# Sheet1.net
KiCad netlist of a schematic drawn in Altium Designer
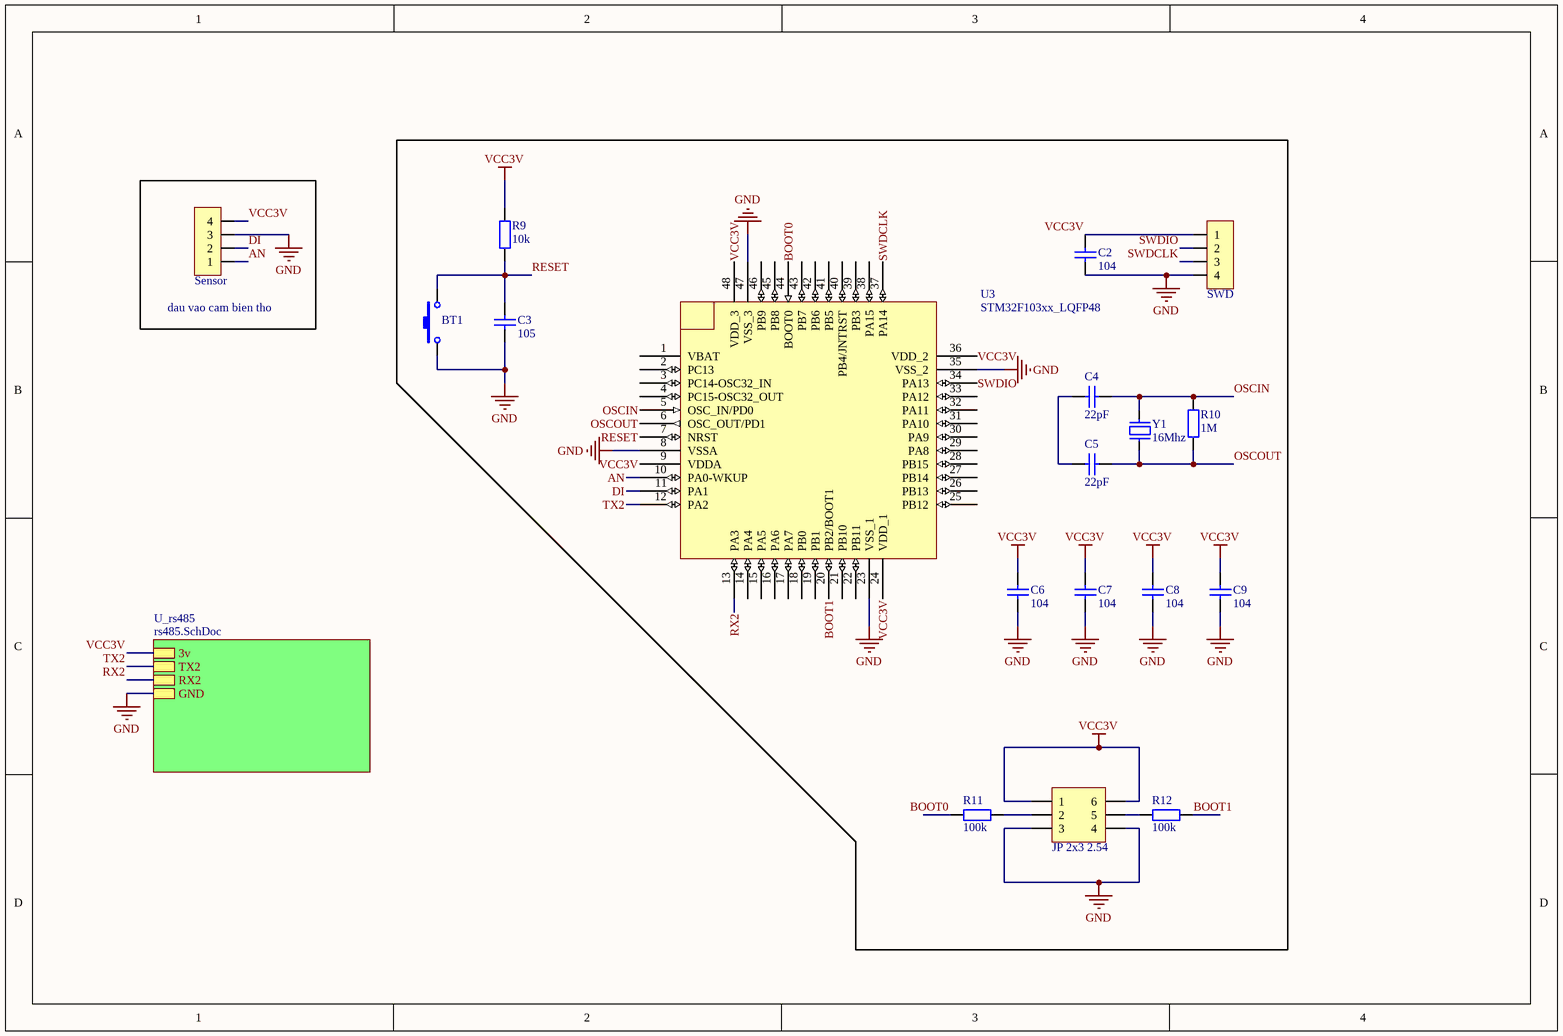
[diagram p0: Sheet1.SchDoc]

(export (version "E")
  (design (tool "Eeschema 10.0.6"))
  (components
    (comp (ref "BT1")
      (value "Nut Nhan 2 Chan SMD 3x6x2.5")
      (footprint "Nut Nhan 2 Chan SMD 3x6x2.5")
      (libsource (lib "Altium_Lib_by_KhueNguyenCreator") (part "Nut Nhan 2 Chan SMD 3x6x2.5"))
    )
    (comp (ref "C2")
      (value "104")
      (footprint "tu 0603")
      (description "Dán")
      (libsource (lib "Altium_Lib_by_KhueNguyenCreator") (part "Tu 0603 104 50V 10%"))
    )
    (comp (ref "C3")
      (value "105")
      (footprint "tu 0603")
      (description "Dán")
      (libsource (lib "Altium_Lib_by_KhueNguyenCreator") (part "Tu 0603 105 16V 20%"))
    )
    (comp (ref "C4")
      (value "22pF")
      (footprint "tu 0603")
      (description "Dán")
      (libsource (lib "Altium_Lib_by_KhueNguyenCreator") (part "Tu 0603 22pF 50V 10%"))
    )
    (comp (ref "C5")
      (value "22pF")
      (footprint "tu 0603")
      (description "Dán")
      (libsource (lib "Altium_Lib_by_KhueNguyenCreator") (part "Tu 0603 22pF 50V 10%"))
    )
    (comp (ref "C6")
      (value "104")
      (footprint "tu 0603")
      (description "Dán")
      (libsource (lib "Altium_Lib_by_KhueNguyenCreator") (part "Tu 0603 104 50V 10%"))
    )
    (comp (ref "C7")
      (value "104")
      (footprint "tu 0603")
      (description "Dán")
      (libsource (lib "Altium_Lib_by_KhueNguyenCreator") (part "Tu 0603 104 50V 10%"))
    )
    (comp (ref "C8")
      (value "104")
      (footprint "tu 0603")
      (description "Dán")
      (libsource (lib "Altium_Lib_by_KhueNguyenCreator") (part "Tu 0603 104 50V 10%"))
    )
    (comp (ref "C9")
      (value "104")
      (footprint "tu 0603")
      (description "Dán")
      (libsource (lib "Altium_Lib_by_KhueNguyenCreator") (part "Tu 0603 104 50V 10%"))
    )
    (comp (ref "JP1")
      (value "Sensor")
      (footprint "JP 1x4 CC")
      (description "Cắm")
      (libsource (lib "Altium_Lib_by_KhueNguyenCreator") (part "JP 1x4 2.54 Cai Cong"))
    )
    (comp (ref "JP2")
      (value "SWD")
      (footprint "JP 1x4 DT")
      (description "Cắm")
      (libsource (lib "Altium_Lib_by_KhueNguyenCreator") (part "JP 1x4 2.54 Duc Thang"))
    )
    (comp (ref "JP3")
      (value "JP 2x3 2.54")
      (footprint "JP 2x3 DT")
      (description "Cắm")
      (libsource (lib "Altium_Lib_by_KhueNguyenCreator") (part "JP 2x3 2.54 Duc Thang"))
    )
    (comp (ref "R9")
      (value "10k")
      (footprint "tro smd 0603")
      (description "Dán")
      (libsource (lib "Altium_Lib_by_KhueNguyenCreator") (part "Tro 0603 5% 10k"))
    )
    (comp (ref "R10")
      (value "1M")
      (footprint "tro smd 0603")
      (description "Dán")
      (libsource (lib "Altium_Lib_by_KhueNguyenCreator") (part "Tro 0603 5% 1M"))
    )
    (comp (ref "R11")
      (value "100k")
      (footprint "tro smd 0603")
      (description "Dán")
      (libsource (lib "Altium_Lib_by_KhueNguyenCreator") (part "Tro 0603 5% 100k"))
    )
    (comp (ref "R12")
      (value "100k")
      (footprint "tro smd 0603")
      (description "Dán")
      (libsource (lib "Altium_Lib_by_KhueNguyenCreator") (part "Tro 0603 5% 100k"))
    )
    (comp (ref "U3")
      (value "STM32F103xx_LQFP48")
      (footprint "STM32_LQPF48")
      (fields (field (name "PUBLISHER") "Altium Limited"))
      (libsource (lib "Altium_Lib_by_KhueNguyenCreator") (part "STM32F103xx_LQFP48"))
    )
    (comp (ref "Y1")
      (value "16Mhz")
      (footprint "Thach Anh 2 chan cam")
      (description "Crystal For all Crystal 2pin.")
      (libsource (lib "Altium_Lib_by_KhueNguyenCreator") (part "Thach Anh 2 chan Cam"))
    )
  )
  (nets
    (net (code "1") (name "/AN") (class "Default")
      (node (ref "JP1") (pin "1") (pinfunction "1_1") (pintype "passive"))
      (node (ref "U3") (pin "10") (pinfunction "PA0-WKUP_10") (pintype "bidirectional"))
    )
    (net (code "2") (name "/BOOT0") (class "Default")
      (node (ref "R11") (pin "1") (pinfunction "1_1") (pintype "passive"))
      (node (ref "U3") (pin "44") (pinfunction "BOOT0_44") (pintype "input"))
    )
    (net (code "3") (name "/BOOT1") (class "Default")
      (node (ref "R12") (pin "2") (pinfunction "2_2") (pintype "passive"))
      (node (ref "U3") (pin "20") (pinfunction "PB2/BOOT1_20") (pintype "bidirectional"))
    )
    (net (code "4") (name "/DI") (class "Default")
      (node (ref "JP1") (pin "2") (pinfunction "2_2") (pintype "passive"))
      (node (ref "U3") (pin "11") (pinfunction "PA1_11") (pintype "bidirectional"))
    )
    (net (code "5") (name "/OSCIN") (class "Default")
      (node (ref "C4") (pin "1") (pinfunction "1_1") (pintype "passive"))
      (node (ref "R10") (pin "2") (pinfunction "2_2") (pintype "passive"))
      (node (ref "U3") (pin "5") (pinfunction "OSC_IN/PD0_5") (pintype "input"))
      (node (ref "Y1") (pin "2") (pinfunction "2_2") (pintype "passive"))
    )
    (net (code "6") (name "/OSCOUT") (class "Default")
      (node (ref "C5") (pin "1") (pinfunction "1_1") (pintype "passive"))
      (node (ref "R10") (pin "1") (pinfunction "1_1") (pintype "passive"))
      (node (ref "U3") (pin "6") (pinfunction "OSC_OUT/PD1_6") (pintype "output"))
      (node (ref "Y1") (pin "1") (pinfunction "1_1") (pintype "passive"))
    )
    (net (code "7") (name "/RESET") (class "Default")
      (node (ref "BT1") (pin "2") (pinfunction "2_2") (pintype "passive"))
      (node (ref "C3") (pin "1") (pinfunction "1_1") (pintype "passive"))
      (node (ref "R9") (pin "1") (pinfunction "1_1") (pintype "passive"))
      (node (ref "U3") (pin "7") (pinfunction "NRST_7") (pintype "bidirectional"))
    )
    (net (code "8") (name "/RX2") (class "Default")
      (node (ref "U3") (pin "13") (pinfunction "PA3_13") (pintype "bidirectional"))
    )
    (net (code "9") (name "/SWDCLK") (class "Default")
      (node (ref "JP2") (pin "3") (pinfunction "3_3") (pintype "passive"))
      (node (ref "U3") (pin "37") (pinfunction "PA14_37") (pintype "bidirectional"))
    )
    (net (code "10") (name "/SWDIO") (class "Default")
      (node (ref "JP2") (pin "2") (pinfunction "2_2") (pintype "passive"))
      (node (ref "U3") (pin "34") (pinfunction "PA13_34") (pintype "bidirectional"))
    )
    (net (code "11") (name "/TX2") (class "Default")
      (node (ref "U3") (pin "12") (pinfunction "PA2_12") (pintype "bidirectional"))
    )
    (net (code "12") (name "GND") (class "Default")
      (node (ref "BT1") (pin "1") (pinfunction "1_1") (pintype "passive"))
      (node (ref "C2") (pin "2") (pinfunction "2_2") (pintype "passive"))
      (node (ref "C3") (pin "2") (pinfunction "2_2") (pintype "passive"))
      (node (ref "C6") (pin "2") (pinfunction "2_2") (pintype "passive"))
      (node (ref "C7") (pin "2") (pinfunction "2_2") (pintype "passive"))
      (node (ref "C8") (pin "2") (pinfunction "2_2") (pintype "passive"))
      (node (ref "C9") (pin "2") (pinfunction "2_2") (pintype "passive"))
      (node (ref "JP1") (pin "3") (pinfunction "3_3") (pintype "passive"))
      (node (ref "JP2") (pin "4") (pinfunction "4_4") (pintype "passive"))
      (node (ref "JP3") (pin "3") (pinfunction "3_3") (pintype "passive"))
      (node (ref "JP3") (pin "4") (pinfunction "4_4") (pintype "passive"))
      (node (ref "U3") (pin "23") (pinfunction "VSS_1_23") (pintype "power_in"))
      (node (ref "U3") (pin "35") (pinfunction "VSS_2_35") (pintype "power_in"))
      (node (ref "U3") (pin "47") (pinfunction "VSS_3_47") (pintype "power_in"))
      (node (ref "U3") (pin "8") (pinfunction "VSSA_8") (pintype "power_in"))
    )
    (net (code "13") (name "Net-(C4-Pad2)") (class "Default")
      (node (ref "C4") (pin "2") (pinfunction "2_2") (pintype "passive"))
      (node (ref "C5") (pin "2") (pinfunction "2_2") (pintype "passive"))
    )
    (net (code "14") (name "Net-(JP3-Pad2)") (class "Default")
      (node (ref "JP3") (pin "2") (pinfunction "2_2") (pintype "passive"))
      (node (ref "R11") (pin "2") (pinfunction "2_2") (pintype "passive"))
    )
    (net (code "15") (name "Net-(JP3-Pad5)") (class "Default")
      (node (ref "JP3") (pin "5") (pinfunction "5_5") (pintype "passive"))
      (node (ref "R12") (pin "1") (pinfunction "1_1") (pintype "passive"))
    )
    (net (code "16") (name "VCC3V") (class "Default")
      (node (ref "C2") (pin "1") (pinfunction "1_1") (pintype "passive"))
      (node (ref "C6") (pin "1") (pinfunction "1_1") (pintype "passive"))
      (node (ref "C7") (pin "1") (pinfunction "1_1") (pintype "passive"))
      (node (ref "C8") (pin "1") (pinfunction "1_1") (pintype "passive"))
      (node (ref "C9") (pin "1") (pinfunction "1_1") (pintype "passive"))
      (node (ref "JP1") (pin "4") (pinfunction "4_4") (pintype "passive"))
      (node (ref "JP2") (pin "1") (pinfunction "1_1") (pintype "passive"))
      (node (ref "JP3") (pin "1") (pinfunction "1_1") (pintype "passive"))
      (node (ref "JP3") (pin "6") (pinfunction "6_6") (pintype "passive"))
      (node (ref "R9") (pin "2") (pinfunction "2_2") (pintype "passive"))
      (node (ref "U3") (pin "24") (pinfunction "VDD_1_24") (pintype "power_in"))
      (node (ref "U3") (pin "36") (pinfunction "VDD_2_36") (pintype "power_in"))
      (node (ref "U3") (pin "48") (pinfunction "VDD_3_48") (pintype "power_in"))
      (node (ref "U3") (pin "9") (pinfunction "VDDA_9") (pintype "power_in"))
    )
    (net (code "17") (name "unconnected-(U3-PA4-Pad14)") (class "Default")
      (node (ref "U3") (pin "14") (pinfunction "PA4_14") (pintype "bidirectional"))
    )
    (net (code "18") (name "unconnected-(U3-PA5-Pad15)") (class "Default")
      (node (ref "U3") (pin "15") (pinfunction "PA5_15") (pintype "bidirectional"))
    )
    (net (code "19") (name "unconnected-(U3-PA6-Pad16)") (class "Default")
      (node (ref "U3") (pin "16") (pinfunction "PA6_16") (pintype "bidirectional"))
    )
    (net (code "20") (name "unconnected-(U3-PA7-Pad17)") (class "Default")
      (node (ref "U3") (pin "17") (pinfunction "PA7_17") (pintype "bidirectional"))
    )
    (net (code "21") (name "unconnected-(U3-PA8-Pad29)") (class "Default")
      (node (ref "U3") (pin "29") (pinfunction "PA8_29") (pintype "bidirectional"))
    )
    (net (code "22") (name "unconnected-(U3-PA9-Pad30)") (class "Default")
      (node (ref "U3") (pin "30") (pinfunction "PA9_30") (pintype "bidirectional"))
    )
    (net (code "23") (name "unconnected-(U3-PA10-Pad31)") (class "Default")
      (node (ref "U3") (pin "31") (pinfunction "PA10_31") (pintype "bidirectional"))
    )
    (net (code "24") (name "unconnected-(U3-PA11-Pad32)") (class "Default")
      (node (ref "U3") (pin "32") (pinfunction "PA11_32") (pintype "bidirectional"))
    )
    (net (code "25") (name "unconnected-(U3-PA12-Pad33)") (class "Default")
      (node (ref "U3") (pin "33") (pinfunction "PA12_33") (pintype "bidirectional"))
    )
    (net (code "26") (name "unconnected-(U3-PA15-Pad38)") (class "Default")
      (node (ref "U3") (pin "38") (pinfunction "PA15_38") (pintype "bidirectional"))
    )
    (net (code "27") (name "unconnected-(U3-PB0-Pad18)") (class "Default")
      (node (ref "U3") (pin "18") (pinfunction "PB0_18") (pintype "bidirectional"))
    )
    (net (code "28") (name "unconnected-(U3-PB1-Pad19)") (class "Default")
      (node (ref "U3") (pin "19") (pinfunction "PB1_19") (pintype "bidirectional"))
    )
    (net (code "29") (name "unconnected-(U3-PB3-Pad39)") (class "Default")
      (node (ref "U3") (pin "39") (pinfunction "PB3_39") (pintype "bidirectional"))
    )
    (net (code "30") (name "unconnected-(U3-PB4{slash}JNTRST-Pad40)") (class "Default")
      (node (ref "U3") (pin "40") (pinfunction "PB4/JNTRST_40") (pintype "bidirectional"))
    )
    (net (code "31") (name "unconnected-(U3-PB5-Pad41)") (class "Default")
      (node (ref "U3") (pin "41") (pinfunction "PB5_41") (pintype "bidirectional"))
    )
    (net (code "32") (name "unconnected-(U3-PB6-Pad42)") (class "Default")
      (node (ref "U3") (pin "42") (pinfunction "PB6_42") (pintype "bidirectional"))
    )
    (net (code "33") (name "unconnected-(U3-PB7-Pad43)") (class "Default")
      (node (ref "U3") (pin "43") (pinfunction "PB7_43") (pintype "bidirectional"))
    )
    (net (code "34") (name "unconnected-(U3-PB8-Pad45)") (class "Default")
      (node (ref "U3") (pin "45") (pinfunction "PB8_45") (pintype "bidirectional"))
    )
    (net (code "35") (name "unconnected-(U3-PB9-Pad46)") (class "Default")
      (node (ref "U3") (pin "46") (pinfunction "PB9_46") (pintype "bidirectional"))
    )
    (net (code "36") (name "unconnected-(U3-PB10-Pad21)") (class "Default")
      (node (ref "U3") (pin "21") (pinfunction "PB10_21") (pintype "bidirectional"))
    )
    (net (code "37") (name "unconnected-(U3-PB11-Pad22)") (class "Default")
      (node (ref "U3") (pin "22") (pinfunction "PB11_22") (pintype "bidirectional"))
    )
    (net (code "38") (name "unconnected-(U3-PB12-Pad25)") (class "Default")
      (node (ref "U3") (pin "25") (pinfunction "PB12_25") (pintype "bidirectional"))
    )
    (net (code "39") (name "unconnected-(U3-PB13-Pad26)") (class "Default")
      (node (ref "U3") (pin "26") (pinfunction "PB13_26") (pintype "bidirectional"))
    )
    (net (code "40") (name "unconnected-(U3-PB14-Pad27)") (class "Default")
      (node (ref "U3") (pin "27") (pinfunction "PB14_27") (pintype "bidirectional"))
    )
    (net (code "41") (name "unconnected-(U3-PB15-Pad28)") (class "Default")
      (node (ref "U3") (pin "28") (pinfunction "PB15_28") (pintype "bidirectional"))
    )
    (net (code "42") (name "unconnected-(U3-PC13-Pad2)") (class "Default")
      (node (ref "U3") (pin "2") (pinfunction "PC13_2") (pintype "bidirectional"))
    )
    (net (code "43") (name "unconnected-(U3-PC14-OSC32_IN-Pad3)") (class "Default")
      (node (ref "U3") (pin "3") (pinfunction "PC14-OSC32_IN_3") (pintype "bidirectional"))
    )
    (net (code "44") (name "unconnected-(U3-PC15-OSC32_OUT-Pad4)") (class "Default")
      (node (ref "U3") (pin "4") (pinfunction "PC15-OSC32_OUT_4") (pintype "bidirectional"))
    )
    (net (code "45") (name "unconnected-(U3-VBAT-Pad1)") (class "Default")
      (node (ref "U3") (pin "1") (pinfunction "VBAT_1") (pintype "power_in"))
    )
  )
)
